# GPIO_Ex.net
KiCad netlist of a schematic drawn in Altium Designer
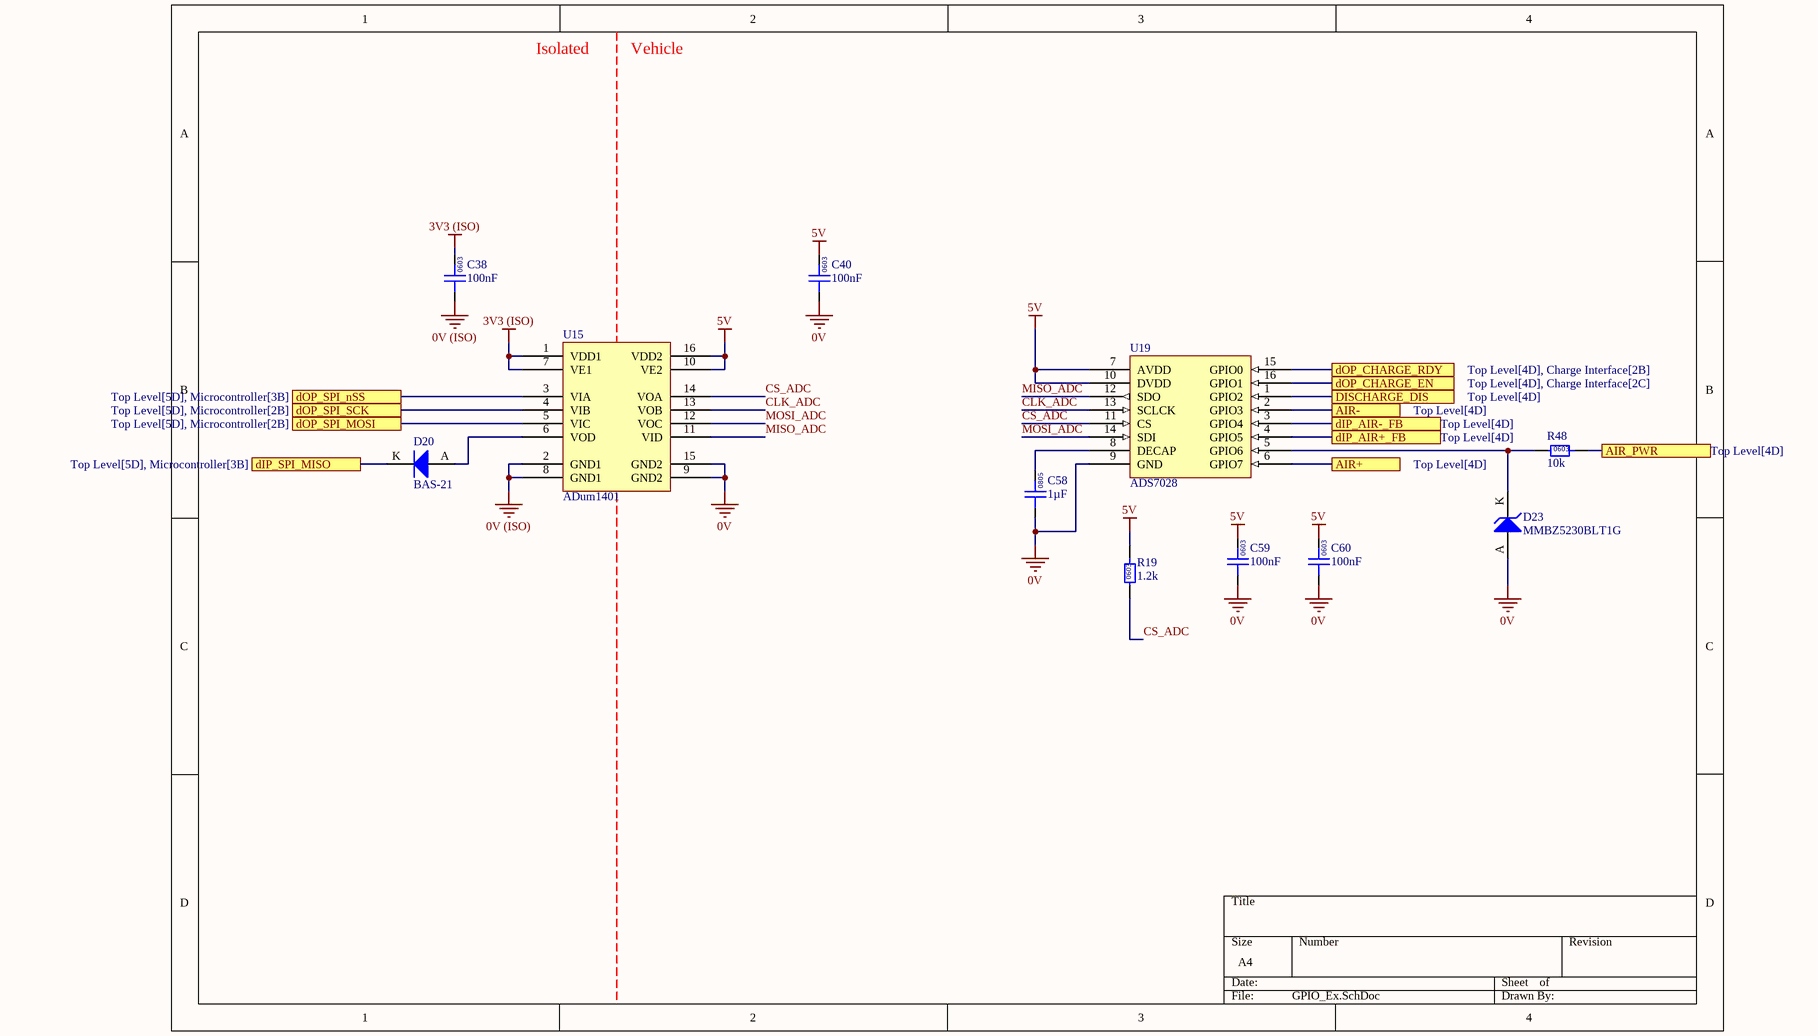
[diagram p0: GPIO_Ex.SchDoc]

(export (version "E")
  (design (tool "Eeschema 10.0.6"))
  (components
    (comp (ref "C38")
      (value "100nF")
      (footprint "0603")
      (fields
        (field (name "PART NUMBER") "GCM188L81H104KA57D")
        (field (name "MANUFACTURER") "muRata")
        (field (name "TOLERANCE") "±10%")
      )
      (libsource (lib "ts_standard_library") (part "Capacitor 0603"))
    )
    (comp (ref "C40")
      (value "100nF")
      (footprint "0603")
      (fields
        (field (name "PART NUMBER") "GCM188L81H104KA57D")
        (field (name "MANUFACTURER") "muRata")
        (field (name "TOLERANCE") "±10%")
      )
      (libsource (lib "ts_standard_library") (part "Capacitor 0603"))
    )
    (comp (ref "C58")
      (value "1µF")
      (footprint "0805")
      (fields
        (field (name "PART NUMBER") "GCM21BR71H105KA03L")
        (field (name "MANUFACTURER") "muRata")
        (field (name "TOLERANCE") "±10%")
      )
      (libsource (lib "ts_standard_library") (part "Capacitor 0805"))
    )
    (comp (ref "C59")
      (value "100nF")
      (footprint "0603")
      (fields
        (field (name "PART NUMBER") "GCM188L81H104KA57D")
        (field (name "MANUFACTURER") "muRata")
        (field (name "TOLERANCE") "±10%")
      )
      (libsource (lib "ts_standard_library") (part "Capacitor 0603"))
    )
    (comp (ref "C60")
      (value "100nF")
      (footprint "0603")
      (fields
        (field (name "PART NUMBER") "GCM188L81H104KA57D")
        (field (name "MANUFACTURER") "muRata")
        (field (name "TOLERANCE") "±10%")
      )
      (libsource (lib "ts_standard_library") (part "Capacitor 0603"))
    )
    (comp (ref "D20")
      (value "BAS-21")
      (footprint "NEXPERIA_SOT23")
      (fields (field (name "MANUFACTURER") "Nexperia USA Inc."))
      (libsource (lib "ts_standard_library") (part "Diode"))
    )
    (comp (ref "D23")
      (value "MMBZ5230BLT1G")
      (footprint "NEXPERIA_SOT23")
      (fields
        (field (name "MANUFACTURER") "onsemi")
        (field (name "DIGIKEY PART NUMBER") "MMBZ5230BLT1GOSTR-ND")
      )
      (libsource (lib "ts_standard_library") (part "Zener Diode"))
    )
    (comp (ref "R19")
      (value "1.2k")
      (footprint "0603")
      (fields
        (field (name "PART NUMBER") "RC0603JR-071K2L")
        (field (name "MANUFACTURER") "YAGEO")
        (field (name "TOLERANCE") "0.01")
      )
      (libsource (lib "ts_standard_library") (part "Resistor 0603"))
    )
    (comp (ref "R48")
      (value "10k")
      (footprint "0603")
      (fields
        (field (name "PART NUMBER") "RC0603FR-0710KL")
        (field (name "MANUFACTURER") "YAGEO")
        (field (name "TOLERANCE") "0.01")
      )
      (libsource (lib "ts_standard_library") (part "Resistor 0603"))
    )
    (comp (ref "U15")
      (value "ADum1401")
      (footprint "AD 16-SOIC")
      (fields (field (name "PART NUMBER") "ADuM1401") (field (name "MANUFACTURER") "Analog Devices"))
      (libsource (lib "ts_standard_library") (part "ADum1401"))
    )
    (comp (ref "U19")
      (value "ADS7028")
      (footprint "WFQN-16")
      (description "IC ADC 12BIT SAR 16WQFN")
      (fields (field (name "PART NUMBER") "ADS7028IRTER") (field (name "MANUFACTURER") "Texas Instruments"))
      (libsource (lib "ts_standard_library") (part "ADS7028IRTER"))
    )
  )
  (nets
    (net (code "1") (name "/AIR+") (class "Default")
      (node (ref "U19") (pin "6") (pinfunction "GPIO7_6") (pintype "input"))
    )
    (net (code "2") (name "/AIR-") (class "Default")
      (node (ref "U19") (pin "2") (pinfunction "GPIO3_2") (pintype "input"))
    )
    (net (code "3") (name "/AIR_PWR") (class "Default")
      (node (ref "R48") (pin "2") (pinfunction "2_2") (pintype "passive"))
    )
    (net (code "4") (name "/CLK_ADC") (class "Default")
      (node (ref "U15") (pin "13") (pinfunction "VOB_13") (pintype "passive"))
      (node (ref "U19") (pin "13") (pinfunction "SCLCK_13") (pintype "input"))
    )
    (net (code "5") (name "/CS_ADC") (class "Default")
      (node (ref "R19") (pin "1") (pinfunction "1_1") (pintype "passive"))
      (node (ref "U15") (pin "14") (pinfunction "VOA_14") (pintype "passive"))
      (node (ref "U19") (pin "11") (pinfunction "CS_11") (pintype "input"))
    )
    (net (code "6") (name "/DISCHARGE_DIS") (class "Default")
      (node (ref "U19") (pin "1") (pinfunction "GPIO2_1") (pintype "input"))
    )
    (net (code "7") (name "/MISO_ADC") (class "Default")
      (node (ref "U15") (pin "11") (pinfunction "VID_11") (pintype "passive"))
      (node (ref "U19") (pin "12") (pinfunction "SDO_12") (pintype "output"))
    )
    (net (code "8") (name "/MOSI_ADC") (class "Default")
      (node (ref "U15") (pin "12") (pinfunction "VOC_12") (pintype "passive"))
      (node (ref "U19") (pin "14") (pinfunction "SDI_14") (pintype "input"))
    )
    (net (code "9") (name "/dIP_AIR+_FB") (class "Default")
      (node (ref "U19") (pin "4") (pinfunction "GPIO5_4") (pintype "input"))
    )
    (net (code "10") (name "/dIP_AIR-_FB") (class "Default")
      (node (ref "U19") (pin "3") (pinfunction "GPIO4_3") (pintype "input"))
    )
    (net (code "11") (name "/dIP_SPI_MISO") (class "Default")
      (node (ref "D20") (pin "K") (pinfunction "K_K") (pintype "passive"))
    )
    (net (code "12") (name "/dOP_CHARGE_EN") (class "Default")
      (node (ref "U19") (pin "16") (pinfunction "GPIO1_16") (pintype "input"))
    )
    (net (code "13") (name "/dOP_CHARGE_RDY") (class "Default")
      (node (ref "U19") (pin "15") (pinfunction "GPIO0_15") (pintype "input"))
    )
    (net (code "14") (name "/dOP_SPI_MOSI") (class "Default")
      (node (ref "U15") (pin "5") (pinfunction "VIC_5") (pintype "passive"))
    )
    (net (code "15") (name "/dOP_SPI_SCK") (class "Default")
      (node (ref "U15") (pin "4") (pinfunction "VIB_4") (pintype "passive"))
    )
    (net (code "16") (name "/dOP_SPI_nSS") (class "Default")
      (node (ref "U15") (pin "3") (pinfunction "VIA_3") (pintype "passive"))
    )
    (net (code "17") (name "0V") (class "Default")
      (node (ref "C40") (pin "1") (pinfunction "1_1") (pintype "passive"))
      (node (ref "C58") (pin "1") (pinfunction "1_1") (pintype "passive"))
      (node (ref "C59") (pin "1") (pinfunction "1_1") (pintype "passive"))
      (node (ref "C60") (pin "1") (pinfunction "1_1") (pintype "passive"))
      (node (ref "D23") (pin "A") (pinfunction "A_A") (pintype "passive"))
      (node (ref "U15") (pin "15") (pinfunction "GND2_15") (pintype "passive"))
      (node (ref "U15") (pin "9") (pinfunction "GND2_9") (pintype "passive"))
      (node (ref "U19") (pin "9") (pinfunction "GND_9") (pintype "power_in"))
    )
    (net (code "18") (name "0V (ISO)") (class "Default")
      (node (ref "C38") (pin "1") (pinfunction "1_1") (pintype "passive"))
      (node (ref "U15") (pin "2") (pinfunction "GND1_2") (pintype "passive"))
      (node (ref "U15") (pin "8") (pinfunction "GND1_8") (pintype "passive"))
    )
    (net (code "19") (name "3V3 (ISO)") (class "Default")
      (node (ref "C38") (pin "2") (pinfunction "2_2") (pintype "passive"))
      (node (ref "U15") (pin "1") (pinfunction "VDD1_1") (pintype "passive"))
      (node (ref "U15") (pin "7") (pinfunction "VE1_7") (pintype "passive"))
    )
    (net (code "20") (name "5V") (class "Default")
      (node (ref "C40") (pin "2") (pinfunction "2_2") (pintype "passive"))
      (node (ref "C59") (pin "2") (pinfunction "2_2") (pintype "passive"))
      (node (ref "C60") (pin "2") (pinfunction "2_2") (pintype "passive"))
      (node (ref "R19") (pin "2") (pinfunction "2_2") (pintype "passive"))
      (node (ref "U15") (pin "10") (pinfunction "VE2_10") (pintype "passive"))
      (node (ref "U15") (pin "16") (pinfunction "VDD2_16") (pintype "passive"))
      (node (ref "U19") (pin "10") (pinfunction "DVDD_10") (pintype "power_in"))
      (node (ref "U19") (pin "7") (pinfunction "AVDD_7") (pintype "power_in"))
    )
    (net (code "21") (name "Net-(U15-VOD)") (class "Default")
      (node (ref "D20") (pin "A") (pinfunction "A_A") (pintype "passive"))
      (node (ref "U15") (pin "6") (pinfunction "VOD_6") (pintype "passive"))
    )
    (net (code "22") (name "Net-(U19-DECAP)") (class "Default")
      (node (ref "C58") (pin "2") (pinfunction "2_2") (pintype "passive"))
      (node (ref "U19") (pin "8") (pinfunction "DECAP_8") (pintype "power_in"))
    )
    (net (code "23") (name "Net-(U19-GPIO6)") (class "Default")
      (node (ref "D23") (pin "K") (pinfunction "K_K") (pintype "passive"))
      (node (ref "R48") (pin "1") (pinfunction "1_1") (pintype "passive"))
      (node (ref "U19") (pin "5") (pinfunction "GPIO6_5") (pintype "input"))
    )
  )
)
